# Sheet1.net
KiCad netlist of a schematic drawn in Altium Designer
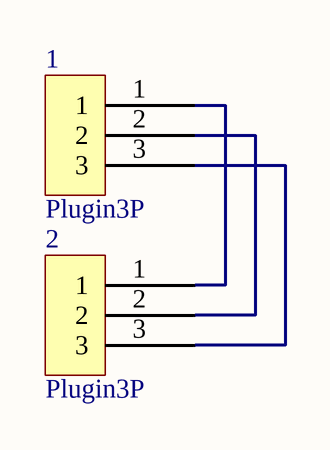
[diagram p0: Sheet1.SchDoc]

(export (version "E")
  (design (tool "Eeschema 10.0.6"))
  (components
    (comp (ref "1") (value "Plugin3P") (footprint "Plugin3P") (libsource (lib "Schlib1") (part "Plugin3P")))
    (comp (ref "2") (value "Plugin3P") (footprint "Plugin3P") (libsource (lib "Schlib1") (part "Plugin3P")))
  )
  (nets
    (net (code "1") (name "Net-(1-Pad1)") (class "Default")
      (node (ref "1") (pin "1") (pinfunction "1_1") (pintype "passive"))
      (node (ref "2") (pin "1") (pinfunction "1_1") (pintype "passive"))
    )
    (net (code "2") (name "Net-(1-Pad2)") (class "Default")
      (node (ref "1") (pin "2") (pinfunction "2_2") (pintype "passive"))
      (node (ref "2") (pin "2") (pinfunction "2_2") (pintype "passive"))
    )
    (net (code "3") (name "Net-(1-Pad3)") (class "Default")
      (node (ref "1") (pin "3") (pinfunction "3_3") (pintype "passive"))
      (node (ref "2") (pin "3") (pinfunction "3_3") (pintype "passive"))
    )
  )
)
